# peripherals.net
KiCad netlist of a schematic drawn in Altium Designer
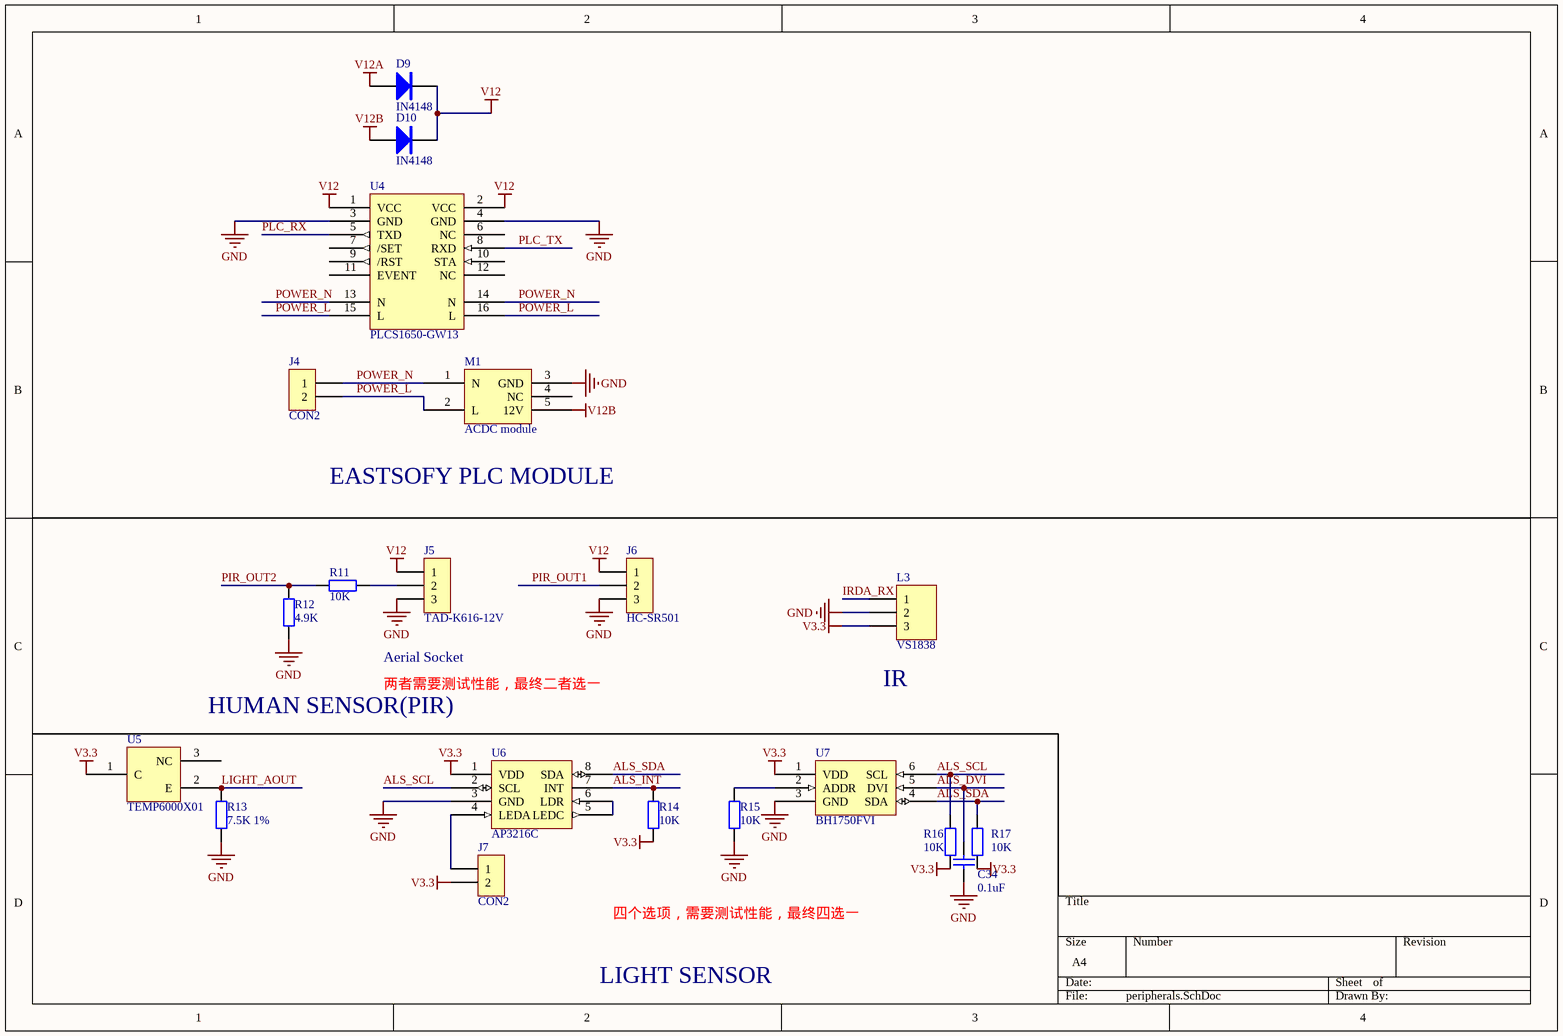
[diagram p0: peripherals.SchDoc]

(export (version "E")
  (design (tool "Eeschema 10.0.6"))
  (components
    (comp (ref "C34")
      (value "0.1uF")
      (footprint "0805C")
      (description "Capacitor")
      (fields (field (name "PUBLISHER") "Altium Limited"))
      (libsource (lib "Miscellaneous Devices") (part "Cap"))
    )
    (comp (ref "D9") (value "IN4148") (footprint "SOD323") (libsource (lib "常用元件库") (part "DIODE")))
    (comp (ref "D10") (value "IN4148") (footprint "SOD323") (libsource (lib "常用元件库") (part "DIODE")))
    (comp (ref "J4") (value "CON2") (footprint "SIP2") (libsource (lib "常用元件库") (part "CON2")))
    (comp (ref "J5")
      (value "TAD-K616-12V")
      (footprint "SIP-3")
      (description "Connector")
      (libsource (lib "Miscellaneous Devices") (part "CON3"))
    )
    (comp (ref "J6")
      (value "HC-SR501")
      (footprint "SIP-3")
      (description "Connector")
      (libsource (lib "Miscellaneous Devices") (part "CON3"))
    )
    (comp (ref "J7") (value "CON2") (footprint "SIP2") (libsource (lib "") (part "CON2_1")))
    (comp (ref "L3")
      (value "VS1838")
      (footprint "HDR1X3")
      (description "Header, 3-Pin")
      (fields (field (name "PUBLISHER") "Altium Limited"))
      (libsource (lib "Miscellaneous Connectors") (part "Header 3"))
    )
    (comp (ref "M1")
      (value "ACDC module")
      (description "220v AC - 12DC module")
      (libsource (lib "work_guyg") (part "ACDC module"))
    )
    (comp (ref "R11")
      (value "10K")
      (footprint "0805R")
      (description "Resistor")
      (fields (field (name "PUBLISHER") "Altium Limited"))
      (libsource (lib "") (part "Res2_1"))
    )
    (comp (ref "R12")
      (value "4.9K")
      (footprint "0805R")
      (description "Resistor")
      (fields (field (name "PUBLISHER") "Altium Limited"))
      (libsource (lib "Miscellaneous Devices") (part "Res2"))
    )
    (comp (ref "R13")
      (value "7.5K 1%")
      (footprint "0805R")
      (description "Resistor")
      (fields (field (name "PUBLISHER") "Altium Limited"))
      (libsource (lib "Miscellaneous Devices") (part "Res2"))
    )
    (comp (ref "R14")
      (value "10K")
      (footprint "0805R")
      (description "Resistor")
      (fields (field (name "PUBLISHER") "Altium Limited"))
      (libsource (lib "Miscellaneous Devices") (part "Res2"))
    )
    (comp (ref "R15")
      (value "10K")
      (footprint "0805R")
      (description "Resistor")
      (fields (field (name "PUBLISHER") "Altium Limited"))
      (libsource (lib "Miscellaneous Devices") (part "Res2"))
    )
    (comp (ref "R16")
      (value "10K")
      (footprint "0805R")
      (description "Resistor")
      (fields (field (name "PUBLISHER") "Altium Limited"))
      (libsource (lib "Miscellaneous Devices") (part "Res2"))
    )
    (comp (ref "R17")
      (value "10K")
      (footprint "0805R")
      (description "Resistor")
      (fields (field (name "PUBLISHER") "Altium Limited"))
      (libsource (lib "Miscellaneous Devices") (part "Res2"))
    )
    (comp (ref "U4")
      (value "PLCS1650-GW13")
      (footprint "PLCS1650-GW13")
      (description "Eastsoft PLC module")
      (libsource (lib "work_guyg") (part "PLCS1650-GW13"))
    )
    (comp (ref "U5")
      (value "TEMP6000X01")
      (footprint "TEMP6000X01")
      (libsource (lib "work_guyg") (part "TEMP6000X01"))
    )
    (comp (ref "U6") (value "AP3216C") (footprint "AP3216C") (libsource (lib "work_guyg") (part "AP3216C")))
    (comp (ref "U7")
      (value "BH1750FVI")
      (footprint "BH1750FVI")
      (libsource (lib "work_guyg") (part "BH1750FVI"))
    )
  )
  (nets
    (net (code "1") (name "/ALS_DVI") (class "Default")
      (node (ref "C34") (pin "1") (pinfunction "1_1") (pintype "passive"))
      (node (ref "U7") (pin "5") (pinfunction "DVI_5") (pintype "input"))
    )
    (net (code "2") (name "/ALS_INT") (class "Default")
      (node (ref "R14") (pin "2") (pinfunction "2_2") (pintype "passive"))
      (node (ref "U6") (pin "7") (pinfunction "INT_7") (pintype "open_collector"))
    )
    (net (code "3") (name "/ALS_SCL") (class "Default")
      (node (ref "R16") (pin "2") (pinfunction "2_2") (pintype "passive"))
      (node (ref "U6") (pin "2") (pinfunction "SCL_2") (pintype "bidirectional"))
      (node (ref "U7") (pin "6") (pinfunction "SCL_6") (pintype "input"))
    )
    (net (code "4") (name "/ALS_SDA") (class "Default")
      (node (ref "R17") (pin "2") (pinfunction "2_2") (pintype "passive"))
      (node (ref "U6") (pin "8") (pinfunction "SDA_8") (pintype "bidirectional"))
      (node (ref "U7") (pin "4") (pinfunction "SDA_4") (pintype "bidirectional"))
    )
    (net (code "5") (name "/IRDA_RX") (class "Default")
      (node (ref "L3") (pin "1") (pinfunction "1_1") (pintype "passive"))
    )
    (net (code "6") (name "/LIGHT_AOUT") (class "Default")
      (node (ref "R13") (pin "2") (pinfunction "2_2") (pintype "passive"))
      (node (ref "U5") (pin "2") (pinfunction "E_2") (pintype "open_emitter"))
    )
    (net (code "7") (name "/PIR_OUT1") (class "Default")
      (node (ref "J6") (pin "2") (pinfunction "2_2") (pintype "passive"))
    )
    (net (code "8") (name "/PIR_OUT2") (class "Default")
      (node (ref "R11") (pin "2") (pinfunction "2_2") (pintype "passive"))
      (node (ref "R12") (pin "2") (pinfunction "2_2") (pintype "passive"))
    )
    (net (code "9") (name "/PLC_RX") (class "Default")
      (node (ref "U4") (pin "5") (pinfunction "TXD_5") (pintype "output"))
    )
    (net (code "10") (name "/PLC_TX") (class "Default")
      (node (ref "U4") (pin "8") (pinfunction "RXD_8") (pintype "input"))
    )
    (net (code "11") (name "/POWER_L") (class "Default")
      (node (ref "J4") (pin "2") (pinfunction "2_2") (pintype "passive"))
      (node (ref "M1") (pin "2") (pinfunction "L_2") (pintype "power_in"))
      (node (ref "U4") (pin "15") (pinfunction "L_15") (pintype "power_in"))
      (node (ref "U4") (pin "16") (pinfunction "L_16") (pintype "power_in"))
    )
    (net (code "12") (name "/POWER_N") (class "Default")
      (node (ref "J4") (pin "1") (pinfunction "1_1") (pintype "passive"))
      (node (ref "M1") (pin "1") (pinfunction "N_1") (pintype "power_in"))
      (node (ref "U4") (pin "13") (pinfunction "N_13") (pintype "power_in"))
      (node (ref "U4") (pin "14") (pinfunction "N_14") (pintype "power_in"))
    )
    (net (code "13") (name "GND") (class "Default")
      (node (ref "C34") (pin "2") (pinfunction "2_2") (pintype "passive"))
      (node (ref "J5") (pin "3") (pinfunction "3_3") (pintype "passive"))
      (node (ref "J6") (pin "3") (pinfunction "3_3") (pintype "passive"))
      (node (ref "L3") (pin "2") (pinfunction "2_2") (pintype "passive"))
      (node (ref "M1") (pin "3") (pinfunction "GND_3") (pintype "power_in"))
      (node (ref "R12") (pin "1") (pinfunction "1_1") (pintype "passive"))
      (node (ref "R13") (pin "1") (pinfunction "1_1") (pintype "passive"))
      (node (ref "R15") (pin "1") (pinfunction "1_1") (pintype "passive"))
      (node (ref "U4") (pin "3") (pinfunction "GND_3") (pintype "power_in"))
      (node (ref "U4") (pin "4") (pinfunction "GND_4") (pintype "power_in"))
      (node (ref "U6") (pin "3") (pinfunction "GND_3") (pintype "power_in"))
      (node (ref "U7") (pin "3") (pinfunction "GND_3") (pintype "power_in"))
    )
    (net (code "14") (name "Net-(J5-Pad2)") (class "Default")
      (node (ref "J5") (pin "2") (pinfunction "2_2") (pintype "passive"))
      (node (ref "R11") (pin "1") (pinfunction "1_1") (pintype "passive"))
    )
    (net (code "15") (name "Net-(U6-LDR)") (class "Default")
      (node (ref "U6") (pin "5") (pinfunction "LEDC_5") (pintype "output"))
      (node (ref "U6") (pin "6") (pinfunction "LDR_6") (pintype "input"))
    )
    (net (code "16") (name "Net-(U6-LEDA)") (class "Default")
      (node (ref "J7") (pin "1") (pinfunction "1_1") (pintype "passive"))
      (node (ref "U6") (pin "4") (pinfunction "LEDA_4") (pintype "input"))
    )
    (net (code "17") (name "Net-(U7-ADDR)") (class "Default")
      (node (ref "R15") (pin "2") (pinfunction "2_2") (pintype "passive"))
      (node (ref "U7") (pin "2") (pinfunction "ADDR_2") (pintype "input"))
    )
    (net (code "18") (name "V3.3") (class "Default")
      (node (ref "J7") (pin "2") (pinfunction "2_2") (pintype "passive"))
      (node (ref "L3") (pin "3") (pinfunction "3_3") (pintype "passive"))
      (node (ref "R14") (pin "1") (pinfunction "1_1") (pintype "passive"))
      (node (ref "R16") (pin "1") (pinfunction "1_1") (pintype "passive"))
      (node (ref "R17") (pin "1") (pinfunction "1_1") (pintype "passive"))
      (node (ref "U5") (pin "1") (pinfunction "C_1") (pintype "open_collector"))
      (node (ref "U6") (pin "1") (pinfunction "VDD_1") (pintype "power_in"))
      (node (ref "U7") (pin "1") (pinfunction "VDD_1") (pintype "power_in"))
    )
    (net (code "19") (name "V12") (class "Default")
      (node (ref "D10") (pin "K") (pinfunction "K_K") (pintype "passive"))
      (node (ref "D9") (pin "K") (pinfunction "K_K") (pintype "passive"))
      (node (ref "J5") (pin "1") (pinfunction "1_1") (pintype "passive"))
      (node (ref "J6") (pin "1") (pinfunction "1_1") (pintype "passive"))
      (node (ref "U4") (pin "1") (pinfunction "VCC_1") (pintype "power_in"))
      (node (ref "U4") (pin "2") (pinfunction "VCC_2") (pintype "power_in"))
    )
    (net (code "20") (name "V12A") (class "Default")
      (node (ref "D9") (pin "A") (pinfunction "A_A") (pintype "passive"))
    )
    (net (code "21") (name "V12B") (class "Default")
      (node (ref "D10") (pin "A") (pinfunction "A_A") (pintype "passive"))
      (node (ref "M1") (pin "5") (pinfunction "12V_5") (pintype "power_in"))
    )
    (net (code "22") (name "unconnected-(M1-NC-Pad4)") (class "Default")
      (node (ref "M1") (pin "4") (pinfunction "NC_4") (pintype "power_in"))
    )
    (net (code "23") (name "unconnected-(U4-EVENT-Pad11)") (class "Default")
      (node (ref "U4") (pin "11") (pinfunction "EVENT_11") (pintype "open_collector"))
    )
    (net (code "24") (name "unconnected-(U4-NC-Pad6)") (class "Default")
      (node (ref "U4") (pin "6") (pinfunction "NC_6") (pintype "passive"))
    )
    (net (code "25") (name "unconnected-(U4-NC-Pad12)") (class "Default")
      (node (ref "U4") (pin "12") (pinfunction "NC_12") (pintype "passive"))
    )
    (net (code "26") (name "unconnected-(U4-STA-Pad10)") (class "Default")
      (node (ref "U4") (pin "10") (pinfunction "STA_10") (pintype "input"))
    )
    (net (code "27") (name "unconnected-(U4-{slash}RST-Pad9)") (class "Default")
      (node (ref "U4") (pin "9") (pinfunction "/RST_9") (pintype "output"))
    )
    (net (code "28") (name "unconnected-(U4-{slash}SET-Pad7)") (class "Default")
      (node (ref "U4") (pin "7") (pinfunction "/SET_7") (pintype "output"))
    )
    (net (code "29") (name "unconnected-(U5-NC-Pad3)") (class "Default")
      (node (ref "U5") (pin "3") (pinfunction "NC_3") (pintype "passive"))
    )
  )
)
